# coprocessor.net
KiCad netlist of a schematic drawn in EAGLE
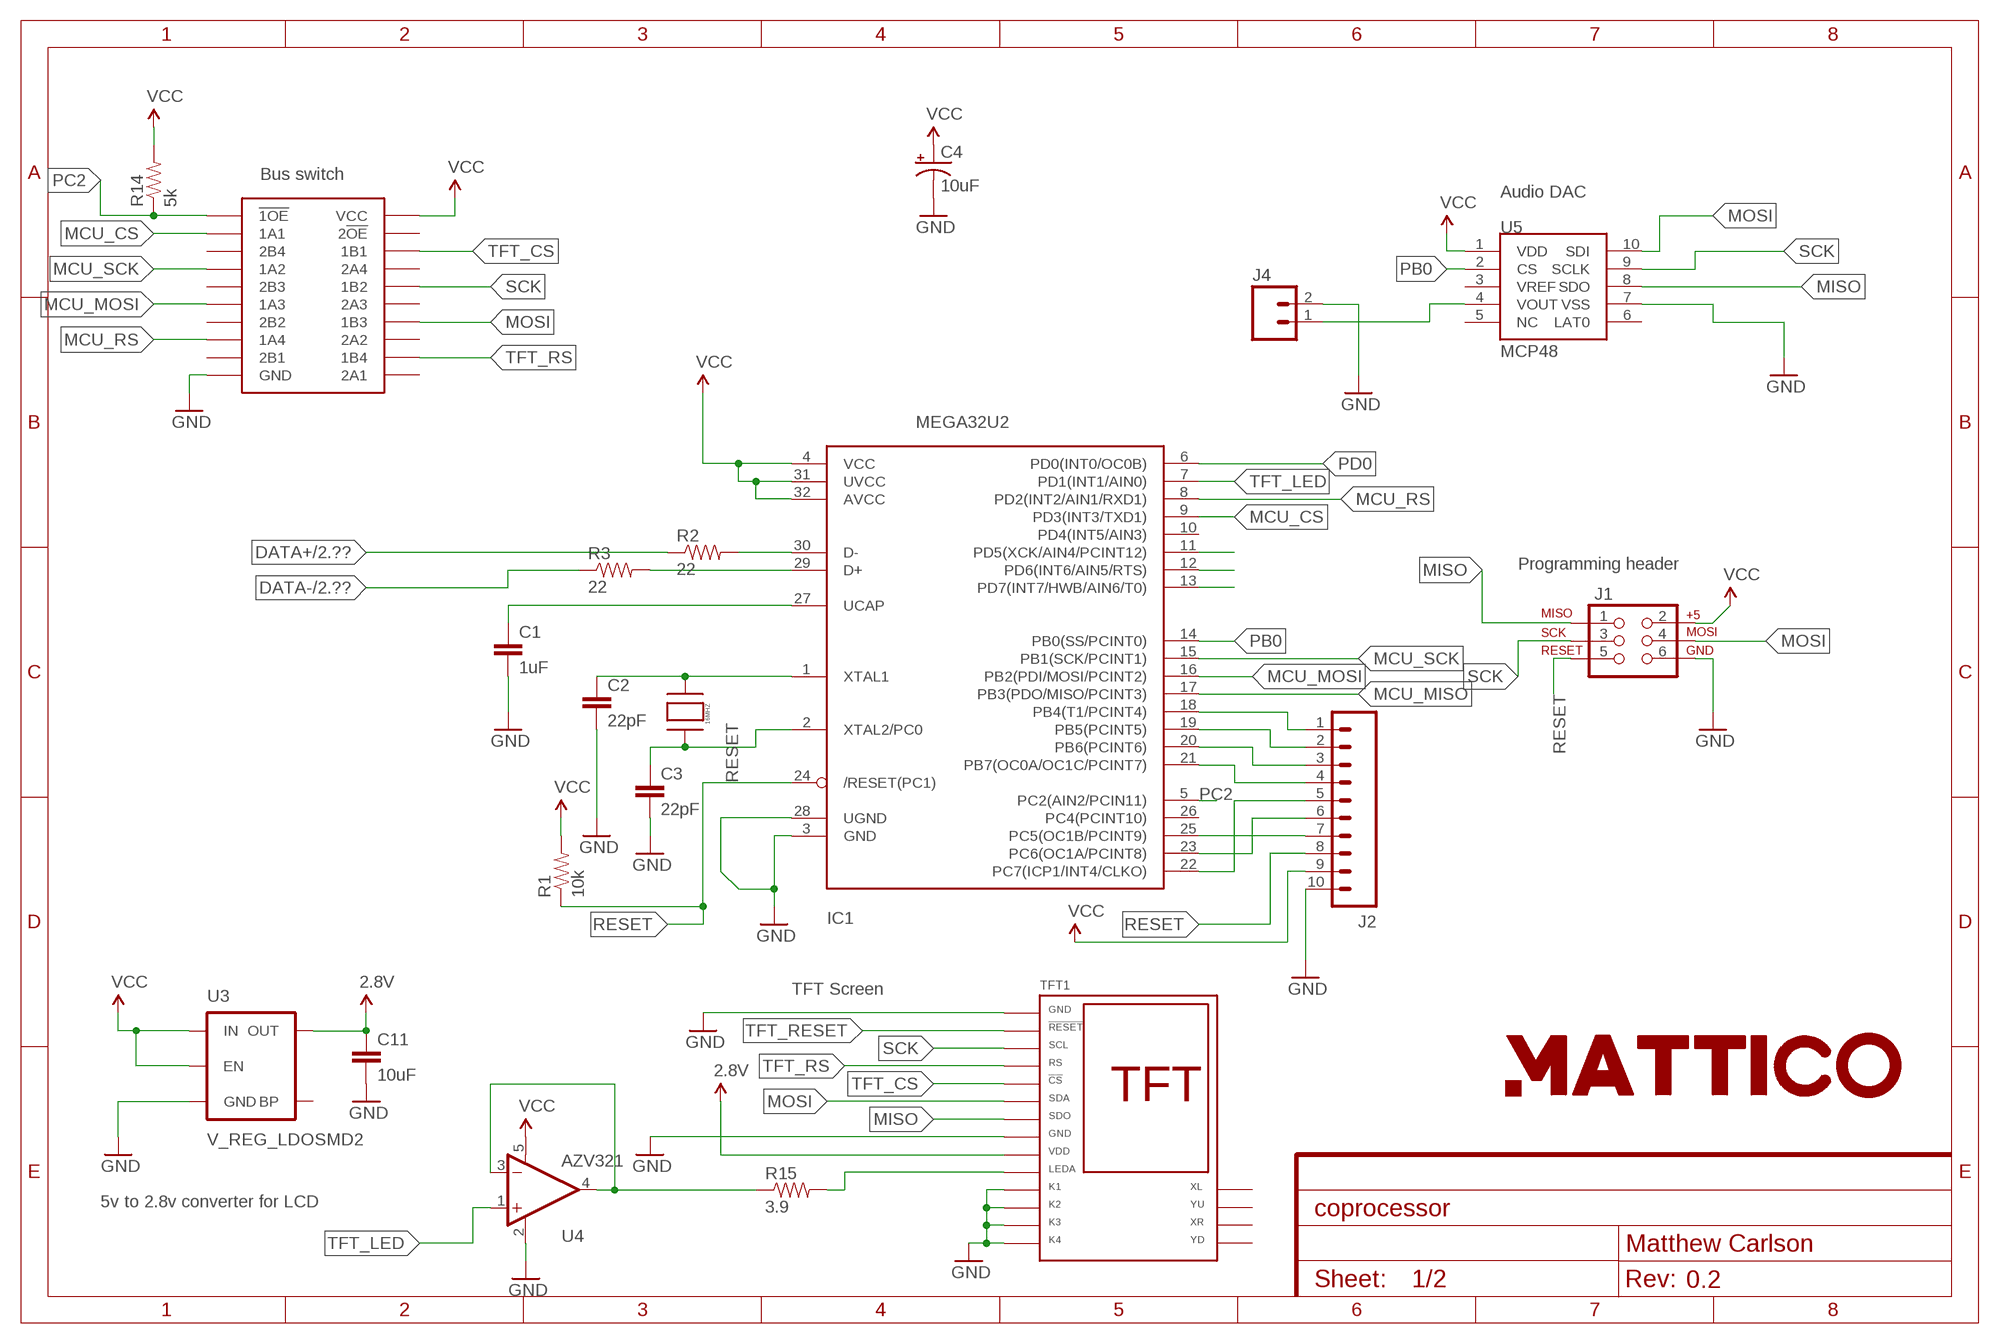
[diagram p0: schematic, sheet 1]
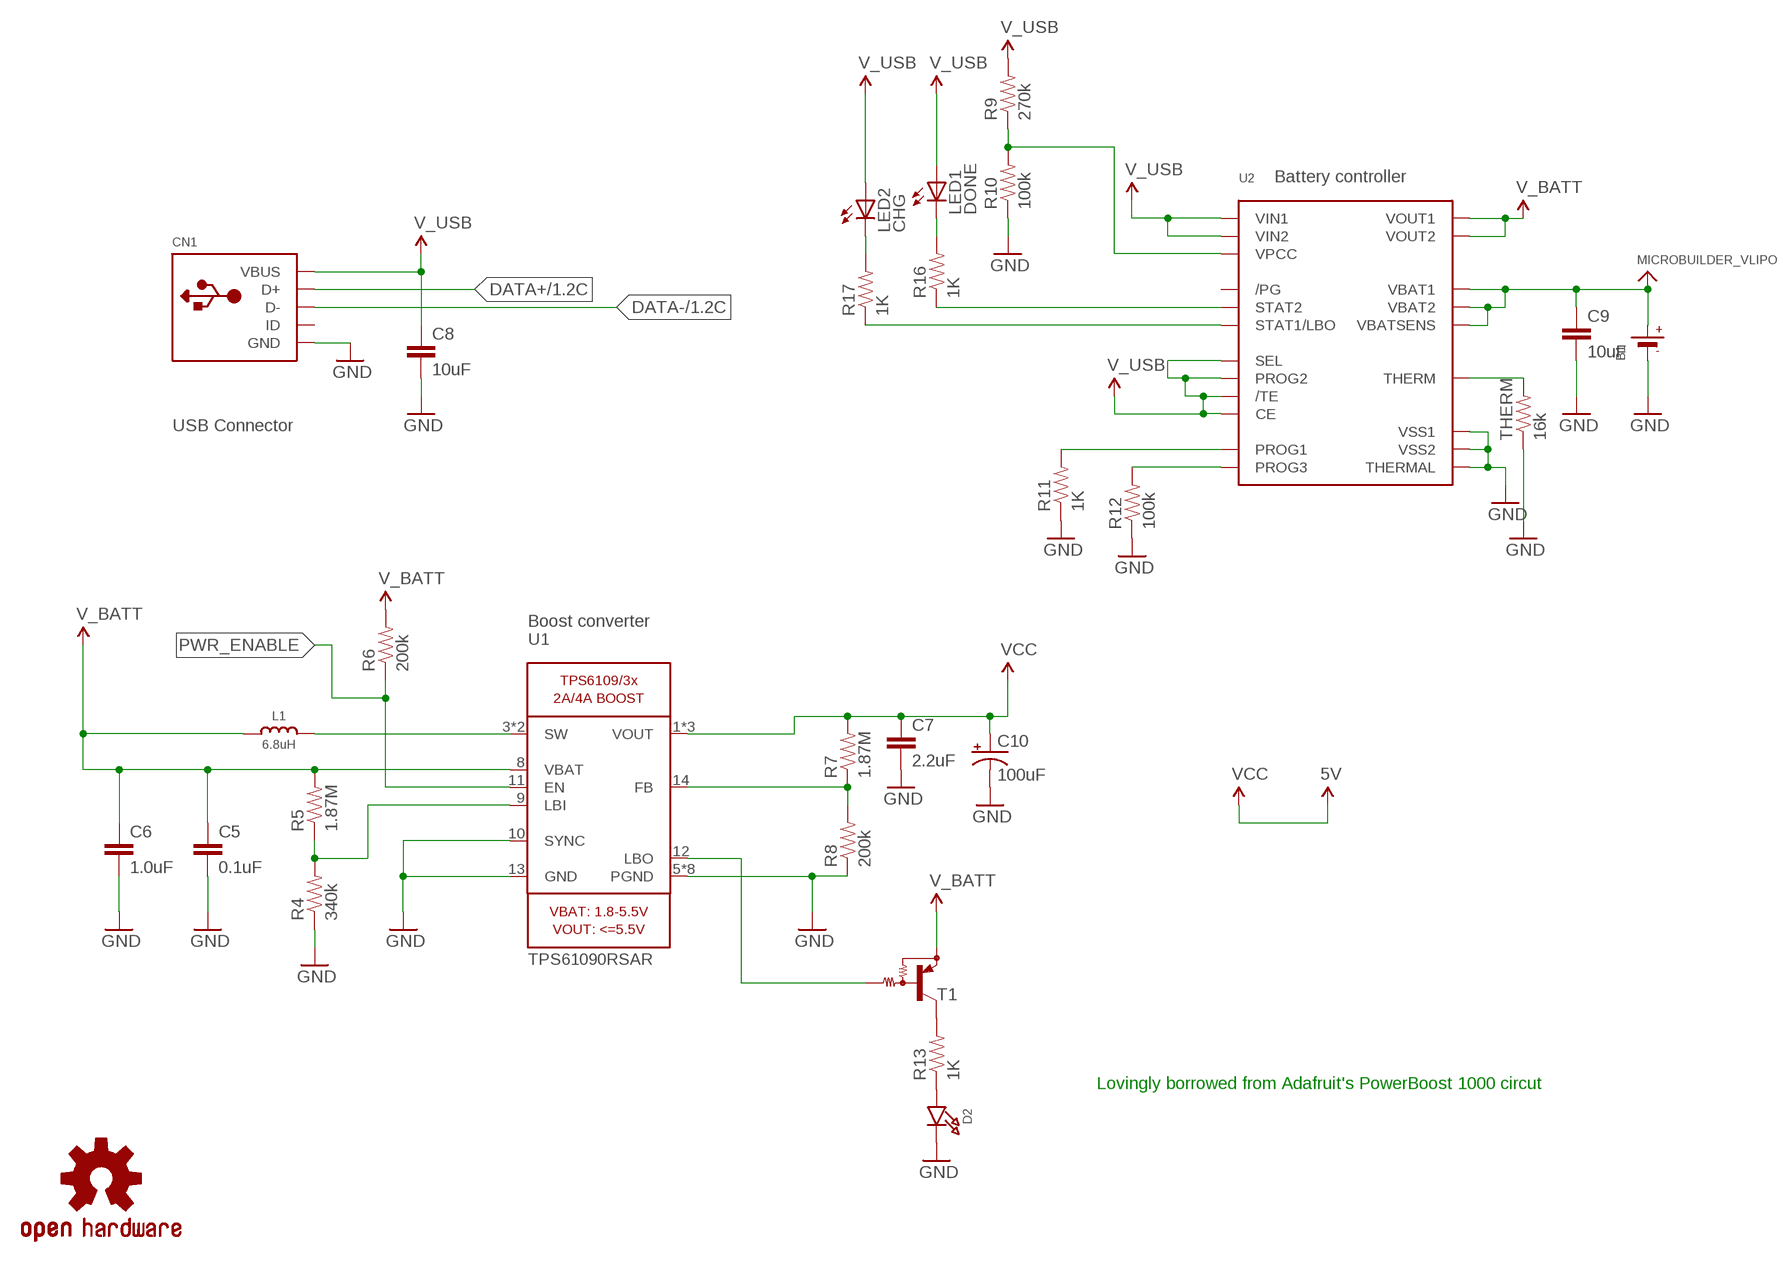
[diagram p1: schematic, sheet 2]

(export (version "E")
  (design (tool "Eeschema 10.0.6"))
  (components
    (comp (ref "C1")
      (value "1uF")
      (footprint "eagle-import:0805")
      (libsource (lib "eagle-import") (part "CAP0805"))
    )
    (comp (ref "C2")
      (value "22pF")
      (footprint "eagle-import:0805")
      (libsource (lib "eagle-import") (part "CAP0805"))
    )
    (comp (ref "C3")
      (value "22pF")
      (footprint "eagle-import:0805")
      (libsource (lib "eagle-import") (part "CAP0805"))
    )
    (comp (ref "C4")
      (value "10uF")
      (footprint "eagle-import:EIA3216")
      (libsource (lib "eagle-import") (part "CAP_POL1206"))
    )
    (comp (ref "C11")
      (value "10uF")
      (footprint "eagle-import:0805-CAP")
      (libsource (lib "eagle-import") (part "10UF10V10%(0805)"))
    )
    (comp (ref "IC1")
      (value "MEGA32U2")
      (footprint "eagle-import:TQFP32-08")
      (libsource (lib "eagle-import") (part "ATMEGA32U2-TQFP"))
    )
    (comp (ref "J1")
      (value "AVR_SPI_PRG_6NS")
      (footprint "eagle-import:2X3-NS")
      (libsource (lib "eagle-import") (part "AVR_SPI_PRG_6NS"))
    )
    (comp (ref "J2")
      (value "M102MM")
      (footprint "eagle-import:1X10-2MM")
      (libsource (lib "eagle-import") (part "M102MM"))
    )
    (comp (ref "J4")
      (value "M02LOCK")
      (footprint "eagle-import:1X02_LOCK")
      (libsource (lib "eagle-import") (part "M02LOCK"))
    )
    (comp (ref "R1")
      (value "10k")
      (footprint "eagle-import:0805")
      (libsource (lib "eagle-import") (part "RESISTOR0805-RES"))
    )
    (comp (ref "R2")
      (value "22")
      (footprint "eagle-import:0805")
      (libsource (lib "eagle-import") (part "RESISTOR0805-RES"))
    )
    (comp (ref "R3")
      (value "22")
      (footprint "eagle-import:0805")
      (libsource (lib "eagle-import") (part "RESISTOR0805-RES"))
    )
    (comp (ref "R14")
      (value "5k")
      (footprint "eagle-import:0805")
      (libsource (lib "eagle-import") (part "RESISTOR0805-RES"))
    )
    (comp (ref "R15")
      (value "3.9")
      (footprint "eagle-import:0805")
      (libsource (lib "eagle-import") (part "RESISTOR0805-RES"))
    )
    (comp (ref "TFT1")
      (value "TFT-18-1.0MM")
      (footprint "eagle-import:TFT-CONN-18")
      (libsource (lib "eagle-import") (part "TFT-18-1.0MM"))
    )
    (comp (ref "U$2")
      (value "LOGO2INCH_SVG")
      (footprint "eagle-import:LOGO_2INCH_SVG")
      (libsource (lib "eagle-import") (part "LOGO2INCH_SVG"))
    )
    (comp (ref "U3")
      (value "V_REG_LDOSMD2")
      (footprint "eagle-import:SC70")
      (libsource (lib "eagle-import") (part "V_REG_LDOSMD2"))
    )
    (comp (ref "U4")
      (value "AZV321")
      (footprint "eagle-import:SOT23-5")
      (libsource (lib "eagle-import") (part "AZV321"))
    )
    (comp (ref "U5")
      (value "MCP48")
      (footprint "eagle-import:10-MSOP")
      (libsource (lib "eagle-import") (part "MCP48FEB01-E/UN"))
    )
    (comp (ref "U6")
      (value "16MHZ")
      (footprint "eagle-import:HC49_US")
      (libsource (lib "eagle-import") (part "CRYSTAL-ABLS"))
    )
    (comp (ref "U7")
      (value "CBT3244AD")
      (footprint "eagle-import:S020-75MM")
      (libsource (lib "eagle-import") (part "CBT3244AD"))
    )
    (comp (ref "B1")
      (value "MICROBUILDER_BATTERY")
      (footprint "eagle-import:MICROBUILDER_JSTPH2")
      (libsource (lib "eagle-import") (part "MICROBUILDER_BATTERY"))
    )
    (comp (ref "C5")
      (value "0.1uF")
      (footprint "eagle-import:0603-CAP")
      (libsource (lib "eagle-import") (part "0.1UF-100V-10%(0603)"))
    )
    (comp (ref "C6")
      (value "1.0uF")
      (footprint "eagle-import:0603-CAP")
      (libsource (lib "eagle-import") (part "1.0UF-16V-10%(0603)"))
    )
    (comp (ref "C7")
      (value "2.2uF")
      (footprint "eagle-import:0603-CAP")
      (libsource (lib "eagle-import") (part "2.2UF-10V-20%(0603)"))
    )
    (comp (ref "C8")
      (value "10uF")
      (footprint "eagle-import:0603-CAP")
      (libsource (lib "eagle-import") (part "10UF-6.3V-20%(0603)"))
    )
    (comp (ref "C9")
      (value "10uF")
      (footprint "eagle-import:0603-CAP")
      (libsource (lib "eagle-import") (part "10UF-6.3V-20%(0603)"))
    )
    (comp (ref "C10")
      (value "100uF")
      (footprint "eagle-import:EIA3216")
      (libsource (lib "eagle-import") (part "CAP_POL1206"))
    )
    (comp (ref "CN1")
      (value "USBMINIB")
      (footprint "eagle-import:USB-MINIB")
      (libsource (lib "eagle-import") (part "USBMINIB"))
    )
    (comp (ref "D2")
      (value "MICROBUILDER_LED0603")
      (footprint "eagle-import:MICROBUILDER_CHIPLED_0603")
      (libsource (lib "eagle-import") (part "MICROBUILDER_LED0603"))
    )
    (comp (ref "L1")
      (value "6.8uH")
      (footprint "eagle-import:MICROBUILDER_INDUCTOR_4.9X4.9MM")
      (libsource (lib "eagle-import") (part "MICROBUILDER_INDUCTOR4.9X4.9MM"))
    )
    (comp (ref "LED1")
      (value "DONE")
      (footprint "eagle-import:CHIPLED_0603")
      (libsource (lib "eagle-import") (part "LEDCHIPLED_0603"))
    )
    (comp (ref "LED2")
      (value "CHG")
      (footprint "eagle-import:CHIPLED_0603")
      (libsource (lib "eagle-import") (part "LEDCHIPLED_0603"))
    )
    (comp (ref "LOGO1")
      (value "OSHW-LOGOS")
      (footprint "eagle-import:OSHW-LOGO-S")
      (libsource (lib "eagle-import") (part "OSHW-LOGOS"))
    )
    (comp (ref "R4")
      (value "340k")
      (footprint "eagle-import:0603-RES")
      (libsource (lib "eagle-import") (part "340OHM-1/10W-1%(0603)"))
    )
    (comp (ref "R5")
      (value "1.87M")
      (footprint "eagle-import:0603-RES")
      (libsource (lib "eagle-import") (part "1.8KOHM1/10W1%(0603)"))
    )
    (comp (ref "R6")
      (value "200k")
      (footprint "eagle-import:0603-RES")
      (libsource (lib "eagle-import") (part "200KOHM1/10W1%(0603)200K"))
    )
    (comp (ref "R7")
      (value "1.87M")
      (footprint "eagle-import:0603-RES")
      (libsource (lib "eagle-import") (part "1.8KOHM1/10W1%(0603)"))
    )
    (comp (ref "R8")
      (value "200k")
      (footprint "eagle-import:0603-RES")
      (libsource (lib "eagle-import") (part "200KOHM1/10W1%(0603)200K"))
    )
    (comp (ref "R9")
      (value "270k")
      (footprint "eagle-import:0603-RES")
      (libsource (lib "eagle-import") (part "220KOHM1/10W1%(0603)"))
    )
    (comp (ref "R10")
      (value "100k")
      (footprint "eagle-import:0603-RES")
      (libsource (lib "eagle-import") (part "100KOHM-1/10W-1%(0603)"))
    )
    (comp (ref "R11")
      (value "1K")
      (footprint "eagle-import:0603-RES")
      (libsource (lib "eagle-import") (part "1KOHM-1/10W-1%(0603)"))
    )
    (comp (ref "R12")
      (value "100k")
      (footprint "eagle-import:0603-RES")
      (libsource (lib "eagle-import") (part "100KOHM-1/10W-1%(0603)"))
    )
    (comp (ref "R13")
      (value "1K")
      (footprint "eagle-import:0603-RES")
      (libsource (lib "eagle-import") (part "1KOHM-1/10W-1%(0603)"))
    )
    (comp (ref "R16")
      (value "1K")
      (footprint "eagle-import:0603-RES")
      (libsource (lib "eagle-import") (part "1KOHM-1/10W-1%(0603)"))
    )
    (comp (ref "R17")
      (value "1K")
      (footprint "eagle-import:0603-RES")
      (libsource (lib "eagle-import") (part "1KOHM-1/10W-1%(0603)"))
    )
    (comp (ref "T1")
      (value "TRANSISTOR_PNP_DRIVERMUN2111T1SC59-BEC")
      (footprint "eagle-import:TRANSISTOR_SC59-BEC")
      (libsource (lib "eagle-import") (part "TRANSISTOR_PNP_DRIVERSC59-BECMUN2111T1"))
    )
    (comp (ref "THERM")
      (value "16k")
      (footprint "eagle-import:0603-RES")
      (libsource (lib "eagle-import") (part "RESISTOR0603-RES"))
    )
    (comp (ref "U1")
      (value "TPS61090RSAR")
      (footprint "eagle-import:MICROBUILDER_PVQFN-16")
      (libsource (lib "eagle-import") (part "TPS6103X"))
    )
    (comp (ref "U2")
      (value "MCP73871")
      (footprint "eagle-import:MICROBUILDER_QFN20_4MM")
      (libsource (lib "eagle-import") (part "MCP73871"))
    )
  )
  (nets
    (net (code "1") (name "2.8V") (class "Default")
      (node (ref "C11") (pin "1") (pinfunction "1_1") (pintype "passive"))
      (node (ref "TFT1") (pin "9") (pinfunction "VDD_9") (pintype "power_in"))
      (node (ref "U3") (pin "5") (pinfunction "OUT_5") (pintype "passive"))
    )
    (net (code "2") (name "5V") (class "Default")
      (node (ref "C10") (pin "A") (pinfunction "+_A") (pintype "passive"))
      (node (ref "C4") (pin "A") (pinfunction "+_A") (pintype "passive"))
      (node (ref "C7") (pin "1") (pinfunction "1_1") (pintype "passive"))
      (node (ref "IC1") (pin "31") (pinfunction "UVCC_31") (pintype "bidirectional"))
      (node (ref "IC1") (pin "32") (pinfunction "AVCC_32") (pintype "bidirectional"))
      (node (ref "IC1") (pin "4") (pinfunction "VCC_4") (pintype "bidirectional"))
      (node (ref "J1") (pin "2") (pinfunction "2_2") (pintype "passive"))
      (node (ref "J2") (pin "9") (pinfunction "9_9") (pintype "passive"))
      (node (ref "R1") (pin "2") (pinfunction "2_2") (pintype "passive"))
      (node (ref "R14") (pin "2") (pinfunction "2_2") (pintype "passive"))
      (node (ref "R7") (pin "2") (pinfunction "2_2") (pintype "passive"))
      (node (ref "U1") (pin "1") (pinfunction "VOUT_1") (pintype "power_in"))
      (node (ref "U1") (pin "15") (pinfunction "VOUT_15") (pintype "power_in"))
      (node (ref "U1") (pin "16") (pinfunction "VOUT_16") (pintype "power_in"))
      (node (ref "U3") (pin "1") (pinfunction "IN_1") (pintype "input"))
      (node (ref "U3") (pin "3") (pinfunction "EN_3") (pintype "input"))
      (node (ref "U4") (pin "5") (pinfunction "V+_5") (pintype "power_in"))
      (node (ref "U5") (pin "1") (pinfunction "VDD_1") (pintype "power_in"))
      (node (ref "U7") (pin "P$20") (pinfunction "VCC_P$20") (pintype "power_in"))
    )
    (net (code "3") (name "DATA+") (class "Default")
      (node (ref "CN1") (pin "D+") (pinfunction "D+_D+") (pintype "bidirectional"))
      (node (ref "R2") (pin "1") (pinfunction "1_1") (pintype "passive"))
    )
    (net (code "4") (name "DATA-") (class "Default")
      (node (ref "CN1") (pin "D-") (pinfunction "D-_D-") (pintype "bidirectional"))
      (node (ref "R3") (pin "1") (pinfunction "1_1") (pintype "passive"))
    )
    (net (code "5") (name "GND") (class "Default")
      (node (ref "B1") (pin "1") (pinfunction "-_1") (pintype "passive"))
      (node (ref "C1") (pin "2") (pinfunction "2_2") (pintype "passive"))
      (node (ref "C10") (pin "C") (pinfunction "-_C") (pintype "passive"))
      (node (ref "C11") (pin "2") (pinfunction "2_2") (pintype "passive"))
      (node (ref "C2") (pin "2") (pinfunction "2_2") (pintype "passive"))
      (node (ref "C3") (pin "2") (pinfunction "2_2") (pintype "passive"))
      (node (ref "C4") (pin "C") (pinfunction "-_C") (pintype "passive"))
      (node (ref "C5") (pin "2") (pinfunction "2_2") (pintype "passive"))
      (node (ref "C6") (pin "2") (pinfunction "2_2") (pintype "passive"))
      (node (ref "C7") (pin "2") (pinfunction "2_2") (pintype "passive"))
      (node (ref "C8") (pin "2") (pinfunction "2_2") (pintype "passive"))
      (node (ref "C9") (pin "2") (pinfunction "2_2") (pintype "passive"))
      (node (ref "CN1") (pin "GND") (pinfunction "GND_GND") (pintype "power_in"))
      (node (ref "D2") (pin "C") (pinfunction "C_C") (pintype "passive"))
      (node (ref "IC1") (pin "28") (pinfunction "UGND_28") (pintype "bidirectional"))
      (node (ref "IC1") (pin "3") (pinfunction "GND_3") (pintype "bidirectional"))
      (node (ref "J1") (pin "6") (pinfunction "6_6") (pintype "passive"))
      (node (ref "J2") (pin "10") (pinfunction "10_10") (pintype "passive"))
      (node (ref "J4") (pin "2") (pinfunction "2_2") (pintype "passive"))
      (node (ref "R10") (pin "1") (pinfunction "1_1") (pintype "passive"))
      (node (ref "R11") (pin "1") (pinfunction "1_1") (pintype "passive"))
      (node (ref "R12") (pin "1") (pinfunction "1_1") (pintype "passive"))
      (node (ref "R4") (pin "1") (pinfunction "1_1") (pintype "passive"))
      (node (ref "R8") (pin "1") (pinfunction "1_1") (pintype "passive"))
      (node (ref "TFT1") (pin "1") (pinfunction "GND_1") (pintype "power_in"))
      (node (ref "TFT1") (pin "11") (pinfunction "K1_11") (pintype "bidirectional"))
      (node (ref "TFT1") (pin "12") (pinfunction "K2_12") (pintype "bidirectional"))
      (node (ref "TFT1") (pin "13") (pinfunction "K3_13") (pintype "bidirectional"))
      (node (ref "TFT1") (pin "14") (pinfunction "K4_14") (pintype "bidirectional"))
      (node (ref "TFT1") (pin "8") (pinfunction "GND_8") (pintype "power_in"))
      (node (ref "THERM") (pin "1") (pinfunction "1_1") (pintype "passive"))
      (node (ref "U1") (pin "10") (pinfunction "SYNC_10") (pintype "input"))
      (node (ref "U1") (pin "13") (pinfunction "GND_13") (pintype "power_in"))
      (node (ref "U1") (pin "5") (pinfunction "PGND_5") (pintype "power_in"))
      (node (ref "U1") (pin "6") (pinfunction "PGND_6") (pintype "power_in"))
      (node (ref "U1") (pin "7") (pinfunction "PGND_7") (pintype "power_in"))
      (node (ref "U1") (pin "P$18") (pinfunction "PGND_P$18") (pintype "power_in"))
      (node (ref "U1") (pin "P$19") (pinfunction "PGND_P$19") (pintype "power_in"))
      (node (ref "U1") (pin "P$20") (pinfunction "PGND_P$20") (pintype "power_in"))
      (node (ref "U1") (pin "P$21") (pinfunction "PGND_P$21") (pintype "power_in"))
      (node (ref "U1") (pin "P$22") (pinfunction "PGND_P$22") (pintype "power_in"))
      (node (ref "U2") (pin "P$10") (pinfunction "VSS1_P$10") (pintype "bidirectional"))
      (node (ref "U2") (pin "P$11") (pinfunction "VSS2_P$11") (pintype "bidirectional"))
      (node (ref "U2") (pin "P$21") (pinfunction "THERMAL_P$21") (pintype "bidirectional"))
      (node (ref "U3") (pin "2") (pinfunction "GND_2") (pintype "input"))
      (node (ref "U4") (pin "2") (pinfunction "V-_2") (pintype "power_in"))
      (node (ref "U5") (pin "7") (pinfunction "VSS_7") (pintype "bidirectional"))
      (node (ref "U7") (pin "P$10") (pinfunction "GND_P$10") (pintype "power_in"))
    )
    (net (code "6") (name "MCU_CS") (class "Default")
      (node (ref "IC1") (pin "9") (pinfunction "PD3(INT3/TXD1)_9") (pintype "bidirectional"))
      (node (ref "U7") (pin "P$2") (pinfunction "1A1_P$2") (pintype "input"))
    )
    (net (code "7") (name "MCU_MISO") (class "Default")
      (node (ref "IC1") (pin "17") (pinfunction "PB3(PDO/MISO/PCINT3)_17") (pintype "bidirectional"))
    )
    (net (code "8") (name "MCU_MOSI") (class "Default")
      (node (ref "IC1") (pin "16") (pinfunction "PB2(PDI/MOSI/PCINT2)_16") (pintype "bidirectional"))
      (node (ref "U7") (pin "P$6") (pinfunction "1A3_P$6") (pintype "input"))
    )
    (net (code "9") (name "MCU_RS") (class "Default")
      (node (ref "IC1") (pin "8") (pinfunction "PD2(INT2/AIN1/RXD1)_8") (pintype "bidirectional"))
      (node (ref "U7") (pin "P$8") (pinfunction "1A4_P$8") (pintype "input"))
    )
    (net (code "10") (name "MCU_SCK") (class "Default")
      (node (ref "IC1") (pin "15") (pinfunction "PB1(SCK/PCINT1)_15") (pintype "bidirectional"))
      (node (ref "U7") (pin "P$4") (pinfunction "1A2_P$4") (pintype "input"))
    )
    (net (code "11") (name "MICROBUILDER_VLIPO") (class "Default")
      (node (ref "B1") (pin "2") (pinfunction "+_2") (pintype "passive"))
      (node (ref "C9") (pin "1") (pinfunction "1_1") (pintype "passive"))
      (node (ref "U2") (pin "P$14") (pinfunction "VBAT1_P$14") (pintype "bidirectional"))
      (node (ref "U2") (pin "P$15") (pinfunction "VBAT2_P$15") (pintype "bidirectional"))
      (node (ref "U2") (pin "P$16") (pinfunction "VBATSENS_P$16") (pintype "bidirectional"))
    )
    (net (code "12") (name "MISO") (class "Default")
      (node (ref "J1") (pin "1") (pinfunction "1_1") (pintype "passive"))
      (node (ref "TFT1") (pin "7") (pinfunction "SDO_7") (pintype "output"))
      (node (ref "U5") (pin "8") (pinfunction "SDO_8") (pintype "output"))
    )
    (net (code "13") (name "MOSI") (class "Default")
      (node (ref "J1") (pin "4") (pinfunction "4_4") (pintype "passive"))
      (node (ref "TFT1") (pin "6") (pinfunction "SDA_6") (pintype "input"))
      (node (ref "U5") (pin "10") (pinfunction "SDI_10") (pintype "input"))
      (node (ref "U7") (pin "P$14") (pinfunction "1B3_P$14") (pintype "output"))
    )
    (net (code "14") (name "Net-(D2-PadA)") (class "Default")
      (node (ref "D2") (pin "A") (pinfunction "A_A") (pintype "passive"))
      (node (ref "R13") (pin "1") (pinfunction "1_1") (pintype "passive"))
    )
    (net (code "15") (name "Net-(IC1-D+)") (class "Default")
      (node (ref "IC1") (pin "29") (pinfunction "D+_29") (pintype "bidirectional"))
      (node (ref "R3") (pin "2") (pinfunction "2_2") (pintype "passive"))
    )
    (net (code "16") (name "Net-(IC1-D-)") (class "Default")
      (node (ref "IC1") (pin "30") (pinfunction "D-_30") (pintype "bidirectional"))
      (node (ref "R2") (pin "2") (pinfunction "2_2") (pintype "passive"))
    )
    (net (code "17") (name "Net-(IC1-PB4(T1{slash}PCINT4))") (class "Default")
      (node (ref "IC1") (pin "18") (pinfunction "PB4(T1/PCINT4)_18") (pintype "bidirectional"))
      (node (ref "J2") (pin "1") (pinfunction "1_1") (pintype "passive"))
    )
    (net (code "18") (name "Net-(IC1-PB5(PCINT5))") (class "Default")
      (node (ref "IC1") (pin "19") (pinfunction "PB5(PCINT5)_19") (pintype "bidirectional"))
      (node (ref "J2") (pin "2") (pinfunction "2_2") (pintype "passive"))
    )
    (net (code "19") (name "Net-(IC1-PB6(PCINT6))") (class "Default")
      (node (ref "IC1") (pin "20") (pinfunction "PB6(PCINT6)_20") (pintype "bidirectional"))
      (node (ref "J2") (pin "3") (pinfunction "3_3") (pintype "passive"))
    )
    (net (code "20") (name "Net-(IC1-PB7(OC0A{slash}OC1C{slash}PCINT7))") (class "Default")
      (node (ref "IC1") (pin "21") (pinfunction "PB7(OC0A/OC1C/PCINT7)_21") (pintype "bidirectional"))
      (node (ref "J2") (pin "4") (pinfunction "4_4") (pintype "passive"))
    )
    (net (code "21") (name "Net-(IC1-PC5(OC1B{slash}PCINT9))") (class "Default")
      (node (ref "IC1") (pin "25") (pinfunction "PC5(OC1B/PCINT9)_25") (pintype "bidirectional"))
      (node (ref "J2") (pin "7") (pinfunction "7_7") (pintype "passive"))
    )
    (net (code "22") (name "Net-(IC1-PC6(OC1A{slash}PCINT8))") (class "Default")
      (node (ref "IC1") (pin "23") (pinfunction "PC6(OC1A/PCINT8)_23") (pintype "bidirectional"))
      (node (ref "J2") (pin "6") (pinfunction "6_6") (pintype "passive"))
    )
    (net (code "23") (name "Net-(IC1-PC7(ICP1{slash}INT4{slash}CLKO))") (class "Default")
      (node (ref "IC1") (pin "22") (pinfunction "PC7(ICP1/INT4/CLKO)_22") (pintype "bidirectional"))
      (node (ref "J2") (pin "5") (pinfunction "5_5") (pintype "passive"))
    )
    (net (code "24") (name "Net-(IC1-UCAP)") (class "Default")
      (node (ref "C1") (pin "1") (pinfunction "1_1") (pintype "passive"))
      (node (ref "IC1") (pin "27") (pinfunction "UCAP_27") (pintype "bidirectional"))
    )
    (net (code "25") (name "Net-(IC1-XTAL1)") (class "Default")
      (node (ref "C2") (pin "1") (pinfunction "1_1") (pintype "passive"))
      (node (ref "IC1") (pin "1") (pinfunction "XTAL1_1") (pintype "bidirectional"))
      (node (ref "U6") (pin "P$2") (pinfunction "P$2_P$2") (pintype "bidirectional"))
    )
    (net (code "26") (name "Net-(IC1-XTAL2{slash}PC0)") (class "Default")
      (node (ref "C3") (pin "1") (pinfunction "1_1") (pintype "passive"))
      (node (ref "IC1") (pin "2") (pinfunction "XTAL2/PC0_2") (pintype "bidirectional"))
      (node (ref "U6") (pin "P$1") (pinfunction "P$1_P$1") (pintype "bidirectional"))
    )
    (net (code "27") (name "Net-(L1-2)") (class "Default")
      (node (ref "L1") (pin "P$2") (pinfunction "2_P$2") (pintype "passive"))
      (node (ref "U1") (pin "3") (pinfunction "SW_3") (pintype "input"))
      (node (ref "U1") (pin "4") (pinfunction "SW_4") (pintype "input"))
    )
    (net (code "28") (name "Net-(LED1-PadC)") (class "Default")
      (node (ref "LED1") (pin "C") (pinfunction "C_C") (pintype "passive"))
      (node (ref "R16") (pin "2") (pinfunction "2_2") (pintype "passive"))
    )
    (net (code "29") (name "Net-(LED2-PadC)") (class "Default")
      (node (ref "LED2") (pin "C") (pinfunction "C_C") (pintype "passive"))
      (node (ref "R17") (pin "2") (pinfunction "2_2") (pintype "passive"))
    )
    (net (code "30") (name "Net-(R13-Pad2)") (class "Default")
      (node (ref "R13") (pin "2") (pinfunction "2_2") (pintype "passive"))
      (node (ref "T1") (pin "C") (pinfunction "C_C") (pintype "passive"))
    )
    (net (code "31") (name "Net-(TFT1-LEDA)") (class "Default")
      (node (ref "R15") (pin "2") (pinfunction "2_2") (pintype "passive"))
      (node (ref "TFT1") (pin "10") (pinfunction "LEDA_10") (pintype "bidirectional"))
    )
    (net (code "32") (name "Net-(U1-FB)") (class "Default")
      (node (ref "R7") (pin "1") (pinfunction "1_1") (pintype "passive"))
      (node (ref "R8") (pin "2") (pinfunction "2_2") (pintype "passive"))
      (node (ref "U1") (pin "14") (pinfunction "FB_14") (pintype "input"))
    )
    (net (code "33") (name "Net-(U1-LBI)") (class "Default")
      (node (ref "R4") (pin "2") (pinfunction "2_2") (pintype "passive"))
      (node (ref "R5") (pin "1") (pinfunction "1_1") (pintype "passive"))
      (node (ref "U1") (pin "9") (pinfunction "LBI_9") (pintype "input"))
    )
    (net (code "34") (name "Net-(U1-LBO)") (class "Default")
      (node (ref "T1") (pin "B") (pinfunction "B_B") (pintype "passive"))
      (node (ref "U1") (pin "12") (pinfunction "LBO_12") (pintype "output"))
    )
    (net (code "35") (name "Net-(U2-PROG1)") (class "Default")
      (node (ref "R11") (pin "2") (pinfunction "2_2") (pintype "passive"))
      (node (ref "U2") (pin "P$13") (pinfunction "PROG1_P$13") (pintype "bidirectional"))
    )
    (net (code "36") (name "Net-(U2-PROG3)") (class "Default")
      (node (ref "R12") (pin "2") (pinfunction "2_2") (pintype "passive"))
      (node (ref "U2") (pin "P$12") (pinfunction "PROG3_P$12") (pintype "bidirectional"))
    )
    (net (code "37") (name "Net-(U2-STAT1{slash}LBO)") (class "Default")
      (node (ref "R17") (pin "1") (pinfunction "1_1") (pintype "passive"))
      (node (ref "U2") (pin "P$8") (pinfunction "STAT1/LBO_P$8") (pintype "bidirectional"))
    )
    (net (code "38") (name "Net-(U2-STAT2)") (class "Default")
      (node (ref "R16") (pin "1") (pinfunction "1_1") (pintype "passive"))
      (node (ref "U2") (pin "P$7") (pinfunction "STAT2_P$7") (pintype "bidirectional"))
    )
    (net (code "39") (name "Net-(U2-THERM)") (class "Default")
      (node (ref "THERM") (pin "2") (pinfunction "2_2") (pintype "passive"))
      (node (ref "U2") (pin "P$5") (pinfunction "THERM_P$5") (pintype "bidirectional"))
    )
    (net (code "40") (name "Net-(U2-VPCC)") (class "Default")
      (node (ref "R10") (pin "2") (pinfunction "2_2") (pintype "passive"))
      (node (ref "R9") (pin "1") (pinfunction "1_1") (pintype "passive"))
      (node (ref "U2") (pin "P$2") (pinfunction "VPCC_P$2") (pintype "bidirectional"))
    )
    (net (code "41") (name "Net-(U4--IN)") (class "Default")
      (node (ref "R15") (pin "1") (pinfunction "1_1") (pintype "passive"))
      (node (ref "U4") (pin "3") (pinfunction "-IN_3") (pintype "input"))
      (node (ref "U4") (pin "4") (pinfunction "OUT_4") (pintype "output"))
    )
    (net (code "42") (name "Net-(U5-VOUT)") (class "Default")
      (node (ref "J4") (pin "1") (pinfunction "1_1") (pintype "passive"))
      (node (ref "U5") (pin "4") (pinfunction "VOUT_4") (pintype "output"))
    )
    (net (code "43") (name "PB0") (class "Default")
      (node (ref "IC1") (pin "14") (pinfunction "PB0(SS/PCINT0)_14") (pintype "bidirectional"))
      (node (ref "U5") (pin "2") (pinfunction "CS_2") (pintype "input"))
    )
    (net (code "44") (name "PC2") (class "Default")
      (node (ref "IC1") (pin "5") (pinfunction "PC2(AIN2/PCIN11)_5") (pintype "bidirectional"))
      (node (ref "R14") (pin "1") (pinfunction "1_1") (pintype "passive"))
      (node (ref "U7") (pin "P$1") (pinfunction "~{1OE}_P$1") (pintype "bidirectional"))
    )
    (net (code "45") (name "PD0") (class "Default")
      (node (ref "IC1") (pin "6") (pinfunction "PD0(INT0/OC0B)_6") (pintype "bidirectional"))
    )
    (net (code "46") (name "PWR_ENABLE") (class "Default")
      (node (ref "R6") (pin "1") (pinfunction "1_1") (pintype "passive"))
      (node (ref "U1") (pin "11") (pinfunction "EN_11") (pintype "input"))
    )
    (net (code "47") (name "RESET") (class "Default")
      (node (ref "IC1") (pin "24") (pinfunction "/RESET(PC1)_24") (pintype "bidirectional"))
      (node (ref "J1") (pin "5") (pinfunction "5_5") (pintype "passive"))
      (node (ref "J2") (pin "8") (pinfunction "8_8") (pintype "passive"))
      (node (ref "R1") (pin "1") (pinfunction "1_1") (pintype "passive"))
    )
    (net (code "48") (name "SCK") (class "Default")
      (node (ref "J1") (pin "3") (pinfunction "3_3") (pintype "passive"))
      (node (ref "TFT1") (pin "3") (pinfunction "SCL_3") (pintype "input"))
      (node (ref "U5") (pin "9") (pinfunction "SCLK_9") (pintype "input"))
      (node (ref "U7") (pin "P$16") (pinfunction "1B2_P$16") (pintype "output"))
    )
    (net (code "49") (name "TFT_CS") (class "Default")
      (node (ref "TFT1") (pin "5") (pinfunction "~{CS}_5") (pintype "input"))
      (node (ref "U7") (pin "P$18") (pinfunction "1B1_P$18") (pintype "output"))
    )
    (net (code "50") (name "TFT_LED") (class "Default")
      (node (ref "IC1") (pin "7") (pinfunction "PD1(INT1/AIN0)_7") (pintype "bidirectional"))
      (node (ref "U4") (pin "1") (pinfunction "+IN_1") (pintype "input"))
    )
    (net (code "51") (name "TFT_RESET") (class "Default")
      (node (ref "TFT1") (pin "2") (pinfunction "~{RESET}_2") (pintype "input"))
    )
    (net (code "52") (name "TFT_RS") (class "Default")
      (node (ref "TFT1") (pin "4") (pinfunction "RS_4") (pintype "input"))
      (node (ref "U7") (pin "P$12") (pinfunction "1B4_P$12") (pintype "output"))
    )
    (net (code "53") (name "V_BATT") (class "Default")
      (node (ref "C5") (pin "1") (pinfunction "1_1") (pintype "passive"))
      (node (ref "C6") (pin "1") (pinfunction "1_1") (pintype "passive"))
      (node (ref "L1") (pin "P$1") (pinfunction "1_P$1") (pintype "passive"))
      (node (ref "R5") (pin "2") (pinfunction "2_2") (pintype "passive"))
      (node (ref "R6") (pin "2") (pinfunction "2_2") (pintype "passive"))
      (node (ref "T1") (pin "E") (pinfunction "E_E") (pintype "passive"))
      (node (ref "U1") (pin "8") (pinfunction "VBAT_8") (pintype "input"))
      (node (ref "U2") (pin "P$1") (pinfunction "VOUT1_P$1") (pintype "bidirectional"))
      (node (ref "U2") (pin "P$20") (pinfunction "VOUT2_P$20") (pintype "bidirectional"))
    )
    (net (code "54") (name "V_USB") (class "Default")
      (node (ref "C8") (pin "1") (pinfunction "1_1") (pintype "passive"))
      (node (ref "CN1") (pin "VBUS") (pinfunction "VBUS_VBUS") (pintype "power_in"))
      (node (ref "LED1") (pin "A") (pinfunction "A_A") (pintype "passive"))
      (node (ref "LED2") (pin "A") (pinfunction "A_A") (pintype "passive"))
      (node (ref "R9") (pin "2") (pinfunction "2_2") (pintype "passive"))
      (node (ref "U2") (pin "P$17") (pinfunction "CE_P$17") (pintype "bidirectional"))
      (node (ref "U2") (pin "P$18") (pinfunction "VIN1_P$18") (pintype "bidirectional"))
      (node (ref "U2") (pin "P$19") (pinfunction "VIN2_P$19") (pintype "bidirectional"))
      (node (ref "U2") (pin "P$3") (pinfunction "SEL_P$3") (pintype "bidirectional"))
      (node (ref "U2") (pin "P$4") (pinfunction "PROG2_P$4") (pintype "bidirectional"))
      (node (ref "U2") (pin "P$9") (pinfunction "/TE_P$9") (pintype "bidirectional"))
    )
    (net (code "55") (name "unconnected-(CN1-PadID)") (class "Default")
      (node (ref "CN1") (pin "ID") (pinfunction "ID_ID") (pintype "bidirectional"))
    )
    (net (code "56") (name "unconnected-(IC1-PC4(PCINT10)-Pad26)") (class "Default")
      (node (ref "IC1") (pin "26") (pinfunction "PC4(PCINT10)_26") (pintype "bidirectional"))
    )
    (net (code "57") (name "unconnected-(IC1-PD4(INT5{slash}AIN3)-Pad10)") (class "Default")
      (node (ref "IC1") (pin "10") (pinfunction "PD4(INT5/AIN3)_10") (pintype "bidirectional"))
    )
    (net (code "58") (name "unconnected-(IC1-PD5(XCK{slash}AIN4{slash}PCINT12)-Pad11)") (class "Default")
      (node (ref "IC1") (pin "11") (pinfunction "PD5(XCK/AIN4/PCINT12)_11") (pintype "bidirectional"))
    )
    (net (code "59") (name "unconnected-(IC1-PD6(INT6{slash}AIN5{slash}RTS)-Pad12)") (class "Default")
      (node (ref "IC1") (pin "12") (pinfunction "PD6(INT6/AIN5/RTS)_12") (pintype "bidirectional"))
    )
    (net (code "60") (name "unconnected-(IC1-PD7(INT7{slash}HWB{slash}AIN6{slash}T0)-Pad13)") (class "Default")
      (node (ref "IC1") (pin "13") (pinfunction "PD7(INT7/HWB/AIN6/T0)_13") (pintype "bidirectional"))
    )
    (net (code "61") (name "unconnected-(TFT1-XL-Pad15)") (class "Default")
      (node (ref "TFT1") (pin "15") (pinfunction "XL_15") (pintype "input"))
    )
    (net (code "62") (name "unconnected-(TFT1-XR-Pad17)") (class "Default")
      (node (ref "TFT1") (pin "17") (pinfunction "XR_17") (pintype "input"))
    )
    (net (code "63") (name "unconnected-(TFT1-YD-Pad18)") (class "Default")
      (node (ref "TFT1") (pin "18") (pinfunction "YD_18") (pintype "input"))
    )
    (net (code "64") (name "unconnected-(TFT1-YU-Pad16)") (class "Default")
      (node (ref "TFT1") (pin "16") (pinfunction "YU_16") (pintype "input"))
    )
    (net (code "65") (name "unconnected-(U2-{slash}PG-PadP$6)") (class "Default")
      (node (ref "U2") (pin "P$6") (pinfunction "/PG_P$6") (pintype "bidirectional"))
    )
    (net (code "66") (name "unconnected-(U3-BP-Pad4)") (class "Default")
      (node (ref "U3") (pin "4") (pinfunction "BP_4") (pintype "input"))
    )
    (net (code "67") (name "unconnected-(U5-LAT0-Pad6)") (class "Default")
      (node (ref "U5") (pin "6") (pinfunction "LAT0_6") (pintype "bidirectional"))
    )
    (net (code "68") (name "unconnected-(U5-NC-Pad5)") (class "Default")
      (node (ref "U5") (pin "5") (pinfunction "NC_5") (pintype "no_connect"))
    )
    (net (code "69") (name "unconnected-(U5-VREF-Pad3)") (class "Default")
      (node (ref "U5") (pin "3") (pinfunction "VREF_3") (pintype "input"))
    )
    (net (code "70") (name "unconnected-(U7-2A1-PadP$11)") (class "Default")
      (node (ref "U7") (pin "P$11") (pinfunction "2A1_P$11") (pintype "input"))
    )
    (net (code "71") (name "unconnected-(U7-2A2-PadP$13)") (class "Default")
      (node (ref "U7") (pin "P$13") (pinfunction "2A2_P$13") (pintype "input"))
    )
    (net (code "72") (name "unconnected-(U7-2A3-PadP$15)") (class "Default")
      (node (ref "U7") (pin "P$15") (pinfunction "2A3_P$15") (pintype "input"))
    )
    (net (code "73") (name "unconnected-(U7-2A4-PadP$17)") (class "Default")
      (node (ref "U7") (pin "P$17") (pinfunction "2A4_P$17") (pintype "input"))
    )
    (net (code "74") (name "unconnected-(U7-2B1-PadP$9)") (class "Default")
      (node (ref "U7") (pin "P$9") (pinfunction "2B1_P$9") (pintype "output"))
    )
    (net (code "75") (name "unconnected-(U7-2B2-PadP$7)") (class "Default")
      (node (ref "U7") (pin "P$7") (pinfunction "2B2_P$7") (pintype "output"))
    )
    (net (code "76") (name "unconnected-(U7-2B3-PadP$5)") (class "Default")
      (node (ref "U7") (pin "P$5") (pinfunction "2B3_P$5") (pintype "output"))
    )
    (net (code "77") (name "unconnected-(U7-2B4-PadP$3)") (class "Default")
      (node (ref "U7") (pin "P$3") (pinfunction "2B4_P$3") (pintype "output"))
    )
    (net (code "78") (name "unconnected-(U7-2~{OE}-PadP$19)") (class "Default")
      (node (ref "U7") (pin "P$19") (pinfunction "2~{OE}_P$19") (pintype "input"))
    )
  )
)
